# ldo-to-sps-patch.net
KiCad netlist of a schematic drawn in EAGLE
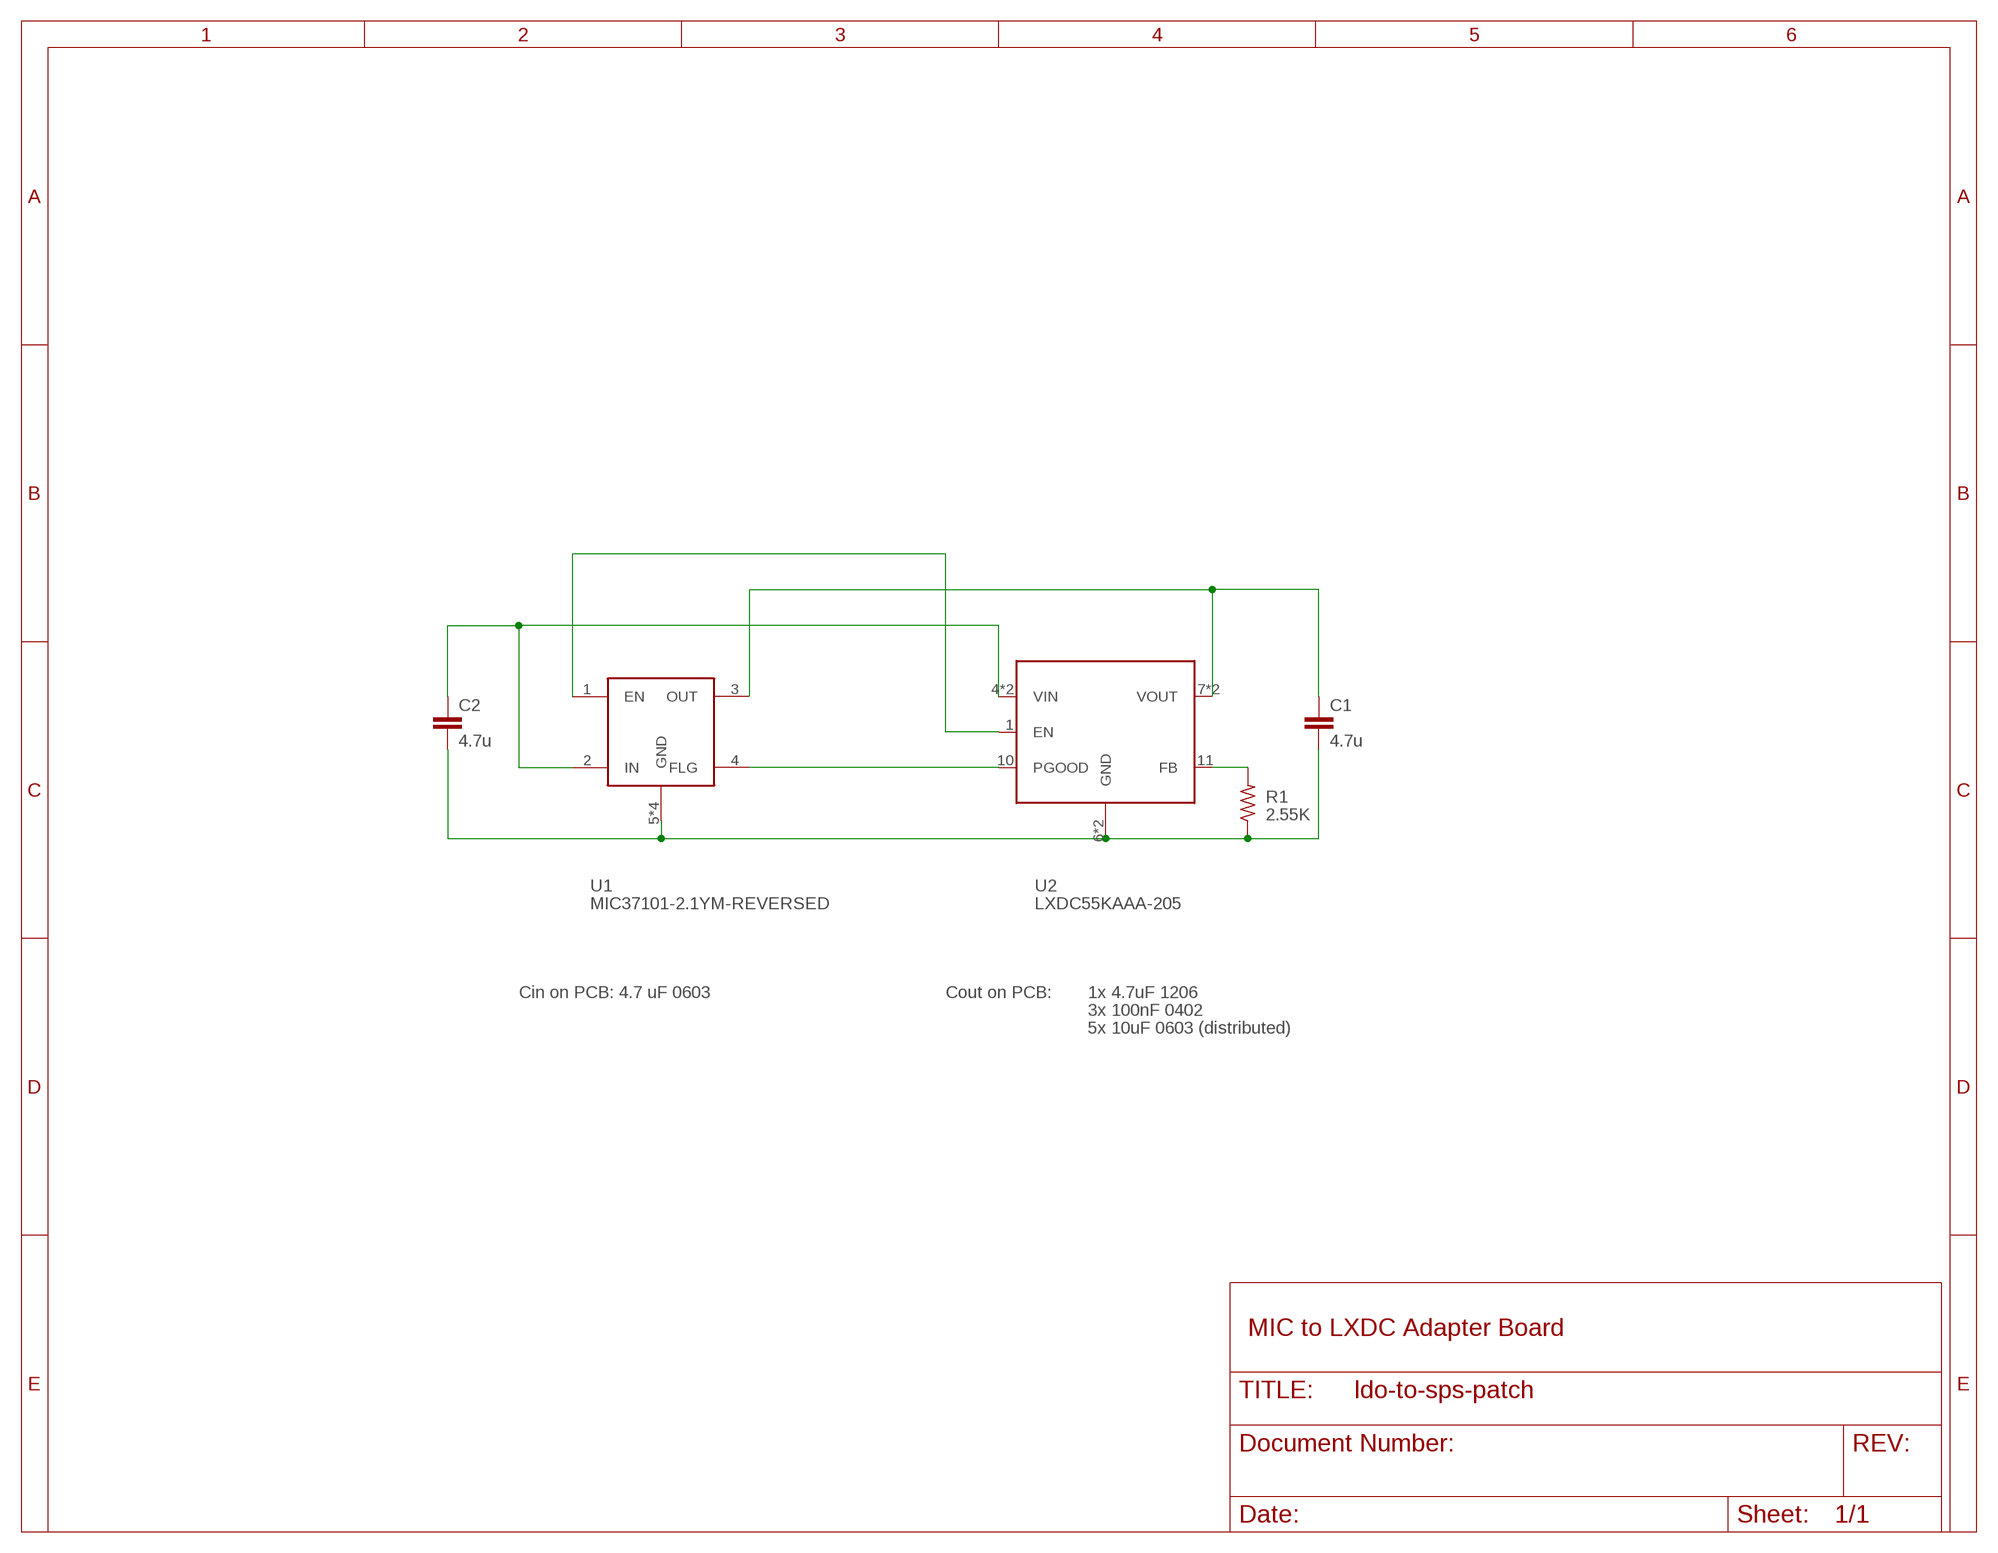
[diagram p0: schematic, sheet 1]

(export (version "E")
  (design (tool "Eeschema 10.0.6"))
  (components
    (comp (ref "C1")
      (value "4.7u")
      (footprint "eagle-import:0402-B-NOSILK")
      (libsource (lib "eagle-import") (part "C-EU0402-B-NOSILK"))
    )
    (comp (ref "C2")
      (value "4.7u")
      (footprint "eagle-import:0402-B-NOSILK")
      (libsource (lib "eagle-import") (part "C-EU0402-B-NOSILK"))
    )
    (comp (ref "R1")
      (value "2.55K")
      (footprint "eagle-import:0402-B-NOSILK")
      (libsource (lib "eagle-import") (part "R-US_0402-B-NOSILK"))
    )
    (comp (ref "U1")
      (value "MIC37101-2.1YM-REVERSED")
      (footprint "eagle-import:SOIC-8-REVERSED")
      (libsource (lib "eagle-import") (part "MIC37101-2.1YM-REVERSED"))
    )
    (comp (ref "U2")
      (value "LXDC55KAAA-205")
      (footprint "eagle-import:LXDC55KAAA-205")
      (libsource (lib "eagle-import") (part "LXDC55KAAA-205"))
    )
  )
  (nets
    (net (code "1") (name "Net-(C1-Pad2)") (class "Default")
      (node (ref "C1") (pin "2") (pinfunction "2_2") (pintype "passive"))
      (node (ref "C2") (pin "2") (pinfunction "2_2") (pintype "passive"))
      (node (ref "R1") (pin "1") (pinfunction "1_1") (pintype "passive"))
      (node (ref "U1") (pin "5") (pinfunction "GND_5") (pintype "bidirectional"))
      (node (ref "U1") (pin "6") (pinfunction "GND_6") (pintype "bidirectional"))
      (node (ref "U1") (pin "7") (pinfunction "GND_7") (pintype "bidirectional"))
      (node (ref "U1") (pin "8") (pinfunction "GND_8") (pintype "bidirectional"))
      (node (ref "U2") (pin "12") (pinfunction "GND_12") (pintype "power_in"))
      (node (ref "U2") (pin "6") (pinfunction "GND_6") (pintype "power_in"))
    )
    (net (code "2") (name "Net-(U1-EN)") (class "Default")
      (node (ref "U1") (pin "1") (pinfunction "EN_1") (pintype "bidirectional"))
      (node (ref "U2") (pin "1") (pinfunction "EN_1") (pintype "input"))
    )
    (net (code "3") (name "Net-(U1-FLG)") (class "Default")
      (node (ref "U1") (pin "4") (pinfunction "FLG_4") (pintype "bidirectional"))
      (node (ref "U2") (pin "10") (pinfunction "PGOOD_10") (pintype "bidirectional"))
    )
    (net (code "4") (name "Net-(U1-IN)") (class "Default")
      (node (ref "C2") (pin "1") (pinfunction "1_1") (pintype "passive"))
      (node (ref "U1") (pin "2") (pinfunction "IN_2") (pintype "bidirectional"))
      (node (ref "U2") (pin "4") (pinfunction "VIN_4") (pintype "power_in"))
      (node (ref "U2") (pin "5") (pinfunction "VIN_5") (pintype "power_in"))
    )
    (net (code "5") (name "Net-(U1-OUT)") (class "Default")
      (node (ref "C1") (pin "1") (pinfunction "1_1") (pintype "passive"))
      (node (ref "U1") (pin "3") (pinfunction "OUT_3") (pintype "bidirectional"))
      (node (ref "U2") (pin "7") (pinfunction "VOUT_7") (pintype "power_in"))
      (node (ref "U2") (pin "8") (pinfunction "VOUT_8") (pintype "power_in"))
    )
    (net (code "6") (name "Net-(U2-FB)") (class "Default")
      (node (ref "R1") (pin "2") (pinfunction "2_2") (pintype "passive"))
      (node (ref "U2") (pin "11") (pinfunction "FB_11") (pintype "passive"))
    )
  )
)
